# PS_control_unit_V3.net
KiCad netlist of a schematic drawn in EAGLE
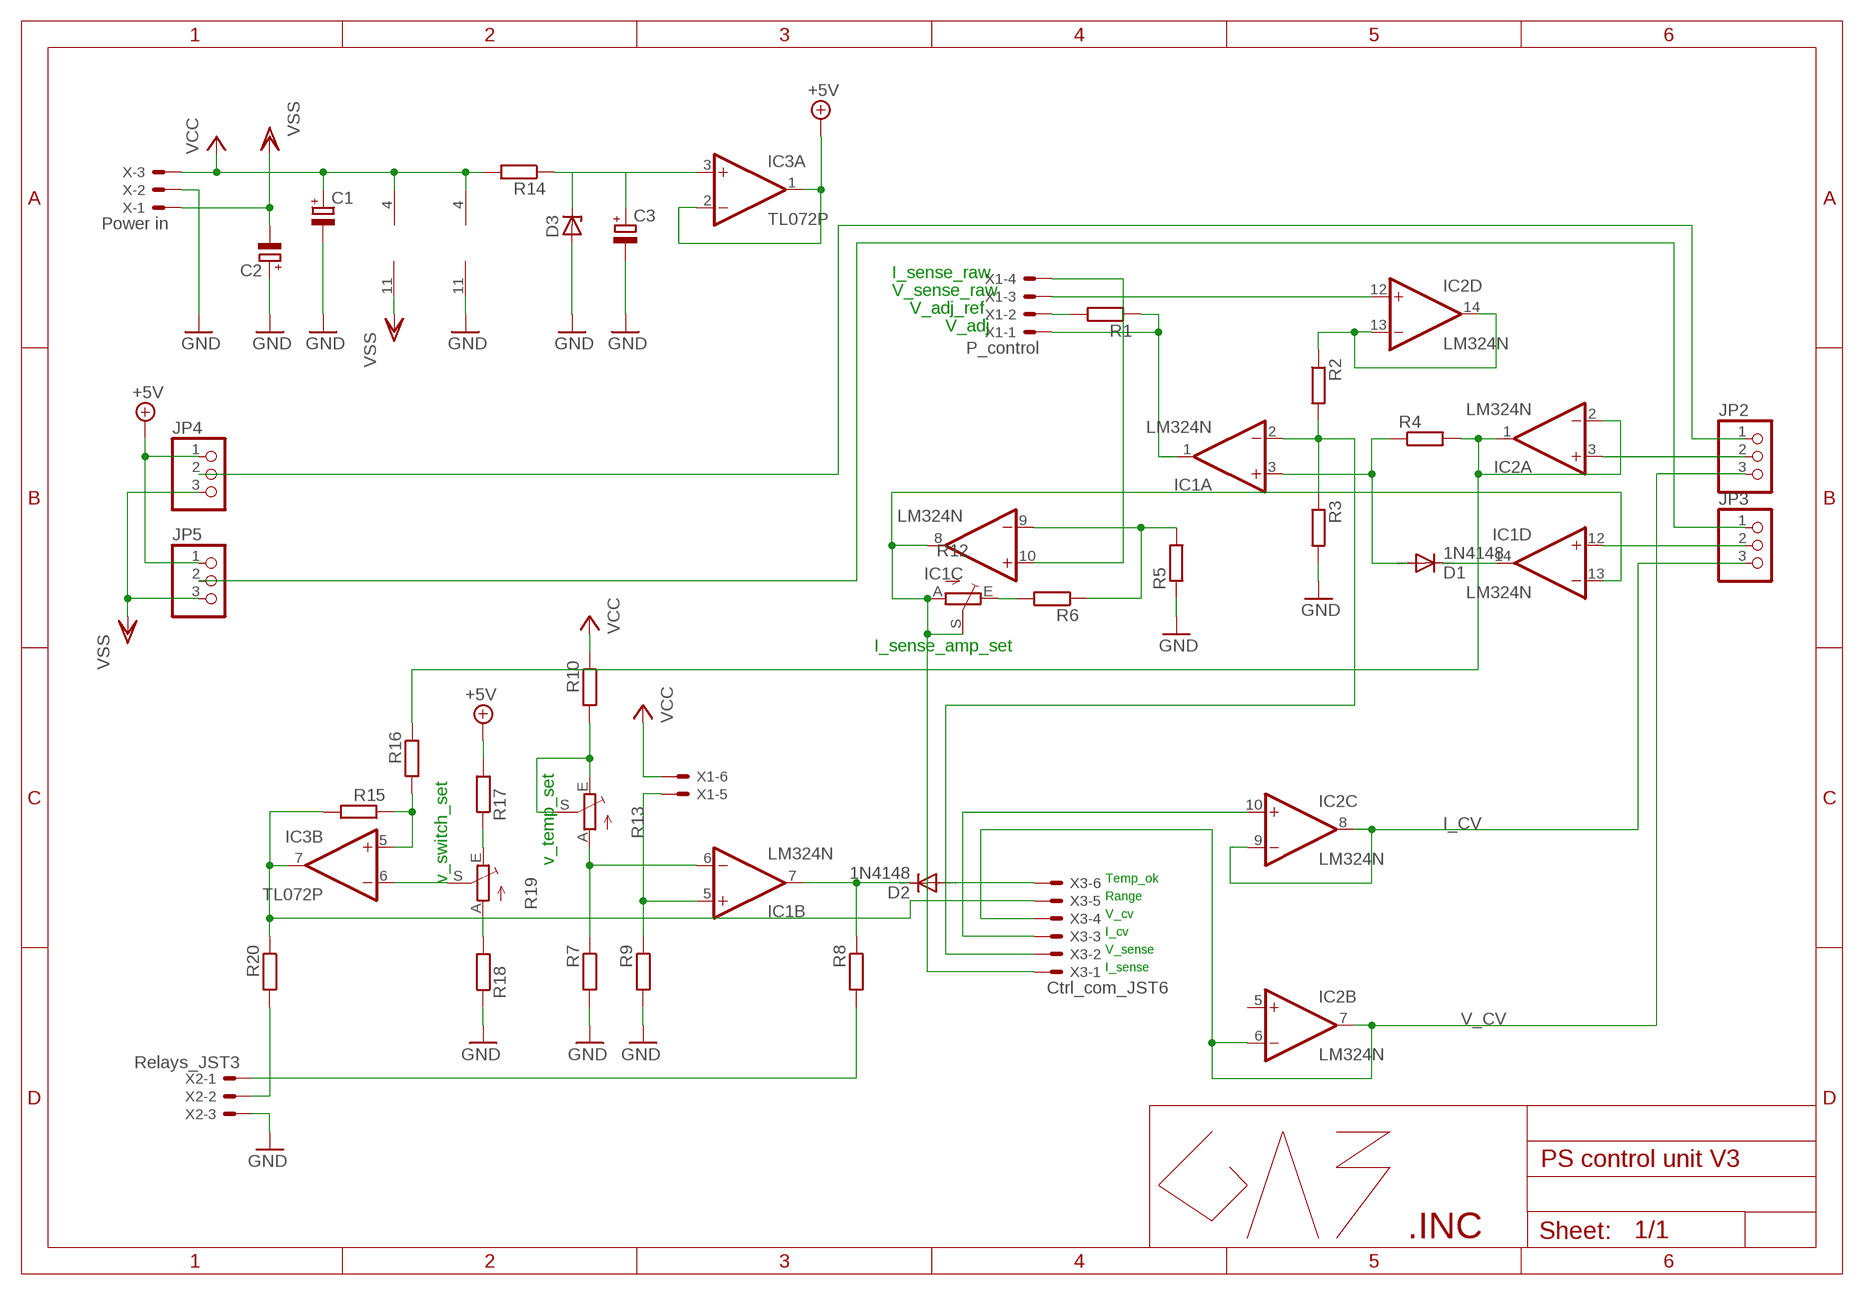
[diagram p0: schematic, sheet 1]

(export (version "E")
  (design (tool "Eeschema 10.0.6"))
  (components
    (comp (ref "C1")
      (value "CPOL-EUE2.5-7")
      (footprint "eagle-import:E2,5-7")
      (libsource (lib "eagle-import") (part "CPOL-EUE2.5-7"))
    )
    (comp (ref "C2")
      (value "CPOL-EUE2-5")
      (footprint "eagle-import:E2-5")
      (libsource (lib "eagle-import") (part "CPOL-EUE2-5"))
    )
    (comp (ref "C3")
      (value "CPOL-EUE2-5")
      (footprint "eagle-import:E2-5")
      (libsource (lib "eagle-import") (part "CPOL-EUE2-5"))
    )
    (comp (ref "D1")
      (value "1N4148")
      (footprint "eagle-import:DO35-10")
      (libsource (lib "eagle-import") (part "1N4148DO35-10"))
    )
    (comp (ref "D2")
      (value "1N4148")
      (footprint "eagle-import:DO35-10")
      (libsource (lib "eagle-import") (part "1N4148DO35-10"))
    )
    (comp (ref "D3")
      (value "ZENER-DIODEDO35Z10")
      (footprint "eagle-import:DO35Z10")
      (libsource (lib "eagle-import") (part "ZENER-DIODEDO35Z10"))
    )
    (comp (ref "IC1")
      (value "LM324N")
      (footprint "eagle-import:DIL14")
      (libsource (lib "eagle-import") (part "LM324N"))
    )
    (comp (ref "IC2")
      (value "LM324N")
      (footprint "eagle-import:DIL14")
      (libsource (lib "eagle-import") (part "LM324N"))
    )
    (comp (ref "IC3")
      (value "TL072P")
      (footprint "eagle-import:DIL08")
      (libsource (lib "eagle-import") (part "TL072P"))
    )
    (comp (ref "JP2")
      (value "PINHD-1X3")
      (footprint "eagle-import:1X03")
      (libsource (lib "eagle-import") (part "PINHD-1X3"))
    )
    (comp (ref "JP3")
      (value "PINHD-1X3")
      (footprint "eagle-import:1X03")
      (libsource (lib "eagle-import") (part "PINHD-1X3"))
    )
    (comp (ref "JP4")
      (value "PINHD-1X3")
      (footprint "eagle-import:1X03")
      (libsource (lib "eagle-import") (part "PINHD-1X3"))
    )
    (comp (ref "JP5")
      (value "PINHD-1X3")
      (footprint "eagle-import:1X03")
      (libsource (lib "eagle-import") (part "PINHD-1X3"))
    )
    (comp (ref "R1")
      (value "R-EU_0309/12")
      (footprint "eagle-import:0309_12")
      (libsource (lib "eagle-import") (part "R-EU_0309/12"))
    )
    (comp (ref "R2")
      (value "R-EU_0207/10")
      (footprint "eagle-import:0207_10")
      (libsource (lib "eagle-import") (part "R-EU_0207/10"))
    )
    (comp (ref "R3")
      (value "R-EU_0207/10")
      (footprint "eagle-import:0207_10")
      (libsource (lib "eagle-import") (part "R-EU_0207/10"))
    )
    (comp (ref "R4")
      (value "R-EU_0207/10")
      (footprint "eagle-import:0207_10")
      (libsource (lib "eagle-import") (part "R-EU_0207/10"))
    )
    (comp (ref "R5")
      (value "R-EU_0207/10")
      (footprint "eagle-import:0207_10")
      (libsource (lib "eagle-import") (part "R-EU_0207/10"))
    )
    (comp (ref "R6")
      (value "R-EU_0207/10")
      (footprint "eagle-import:0207_10")
      (libsource (lib "eagle-import") (part "R-EU_0207/10"))
    )
    (comp (ref "R7")
      (value "R-EU_0207/10")
      (footprint "eagle-import:0207_10")
      (libsource (lib "eagle-import") (part "R-EU_0207/10"))
    )
    (comp (ref "R8")
      (value "R-EU_0207/10")
      (footprint "eagle-import:0207_10")
      (libsource (lib "eagle-import") (part "R-EU_0207/10"))
    )
    (comp (ref "R9")
      (value "R-EU_0207/10")
      (footprint "eagle-import:0207_10")
      (libsource (lib "eagle-import") (part "R-EU_0207/10"))
    )
    (comp (ref "R10")
      (value "R-EU_0207/10")
      (footprint "eagle-import:0207_10")
      (libsource (lib "eagle-import") (part "R-EU_0207/10"))
    )
    (comp (ref "R12")
      (value "TRIM_EU-S64W")
      (footprint "eagle-import:S64W")
      (libsource (lib "eagle-import") (part "TRIM_EU-S64W"))
    )
    (comp (ref "R13")
      (value "TRIM_EU-S64W")
      (footprint "eagle-import:S64W")
      (libsource (lib "eagle-import") (part "TRIM_EU-S64W"))
    )
    (comp (ref "R14")
      (value "R-EU_0309/12")
      (footprint "eagle-import:0309_12")
      (libsource (lib "eagle-import") (part "R-EU_0309/12"))
    )
    (comp (ref "R15")
      (value "R-EU_0207/10")
      (footprint "eagle-import:0207_10")
      (libsource (lib "eagle-import") (part "R-EU_0207/10"))
    )
    (comp (ref "R16")
      (value "R-EU_0207/10")
      (footprint "eagle-import:0207_10")
      (libsource (lib "eagle-import") (part "R-EU_0207/10"))
    )
    (comp (ref "R17")
      (value "R-EU_0207/10")
      (footprint "eagle-import:0207_10")
      (libsource (lib "eagle-import") (part "R-EU_0207/10"))
    )
    (comp (ref "R18")
      (value "R-EU_0207/10")
      (footprint "eagle-import:0207_10")
      (libsource (lib "eagle-import") (part "R-EU_0207/10"))
    )
    (comp (ref "R19")
      (value "TRIM_EU-S64W")
      (footprint "eagle-import:S64W")
      (libsource (lib "eagle-import") (part "TRIM_EU-S64W"))
    )
    (comp (ref "R20")
      (value "R-EU_0207/10")
      (footprint "eagle-import:0207_10")
      (libsource (lib "eagle-import") (part "R-EU_0207/10"))
    )
    (comp (ref "X")
      (value "Power in")
      (footprint "eagle-import:JST-XH-03-PACKAGE-LONG-PAD")
      (libsource (lib "eagle-import") (part "JST-XH-03-PIN-LONG-PAD"))
    )
    (comp (ref "X1")
      (value "P_control")
      (footprint "eagle-import:JST-XH-06-PACKAGE-LONG-PAD")
      (libsource (lib "eagle-import") (part "JST-XH-06-PIN-LONG-PAD"))
    )
    (comp (ref "X2")
      (value "Relays_JST3")
      (footprint "eagle-import:JST-XH-03-PACKAGE-LONG-PAD")
      (libsource (lib "eagle-import") (part "JST-XH-03-PIN-LONG-PAD"))
    )
    (comp (ref "X3")
      (value "Ctrl_com_JST6")
      (footprint "eagle-import:JST-XH-06-PACKAGE-LONG-PAD")
      (libsource (lib "eagle-import") (part "JST-XH-06-PIN-LONG-PAD"))
    )
  )
  (nets
    (net (code "1") (name "+5V") (class "Default")
      (node (ref "IC3") (pin "1") (pinfunction "OUT_1") (pintype "output"))
      (node (ref "IC3") (pin "2") (pinfunction "-IN_2") (pintype "input"))
      (node (ref "JP4") (pin "1") (pinfunction "1_1") (pintype "passive"))
      (node (ref "JP5") (pin "1") (pinfunction "1_1") (pintype "passive"))
      (node (ref "R17") (pin "2") (pinfunction "2_2") (pintype "passive"))
    )
    (net (code "2") (name "/I_CV") (class "Default")
      (node (ref "IC2") (pin "8") (pinfunction "OUT_8") (pintype "output"))
      (node (ref "IC2") (pin "9") (pinfunction "-IN_9") (pintype "input"))
      (node (ref "JP3") (pin "3") (pinfunction "3_3") (pintype "passive"))
    )
    (net (code "3") (name "/V_CV") (class "Default")
      (node (ref "IC2") (pin "6") (pinfunction "-IN_6") (pintype "input"))
      (node (ref "IC2") (pin "7") (pinfunction "OUT_7") (pintype "output"))
      (node (ref "JP2") (pin "3") (pinfunction "3_3") (pintype "passive"))
      (node (ref "X3") (pin "4") (pinfunction "S_4") (pintype "passive"))
    )
    (net (code "4") (name "GND") (class "Default")
      (node (ref "C1") (pin "-") (pinfunction "-_-") (pintype "passive"))
      (node (ref "C2") (pin "+") (pinfunction "+_+") (pintype "passive"))
      (node (ref "C3") (pin "-") (pinfunction "-_-") (pintype "passive"))
      (node (ref "D3") (pin "A") (pinfunction "A_A") (pintype "passive"))
      (node (ref "IC2") (pin "11") (pinfunction "V-_11") (pintype "power_in"))
      (node (ref "R18") (pin "1") (pinfunction "1_1") (pintype "passive"))
      (node (ref "R3") (pin "2") (pinfunction "2_2") (pintype "passive"))
      (node (ref "R5") (pin "1") (pinfunction "1_1") (pintype "passive"))
      (node (ref "R7") (pin "2") (pinfunction "2_2") (pintype "passive"))
      (node (ref "R9") (pin "2") (pinfunction "2_2") (pintype "passive"))
      (node (ref "X") (pin "2") (pinfunction "S_2") (pintype "passive"))
      (node (ref "X2") (pin "3") (pinfunction "S_3") (pintype "passive"))
    )
    (net (code "5") (name "Net-(IC1A-+IN)") (class "Default")
      (node (ref "D1") (pin "A") (pinfunction "A_A") (pintype "passive"))
      (node (ref "IC1") (pin "3") (pinfunction "+IN_3") (pintype "input"))
      (node (ref "R4") (pin "1") (pinfunction "1_1") (pintype "passive"))
    )
    (net (code "6") (name "Net-(IC1A--IN)") (class "Default")
      (node (ref "IC1") (pin "2") (pinfunction "-IN_2") (pintype "input"))
      (node (ref "R2") (pin "2") (pinfunction "2_2") (pintype "passive"))
      (node (ref "R3") (pin "1") (pinfunction "1_1") (pintype "passive"))
      (node (ref "X3") (pin "2") (pinfunction "S_2") (pintype "passive"))
    )
    (net (code "7") (name "Net-(IC1A-OUT)") (class "Default")
      (node (ref "IC1") (pin "1") (pinfunction "OUT_1") (pintype "output"))
      (node (ref "R1") (pin "1") (pinfunction "1_1") (pintype "passive"))
      (node (ref "X1") (pin "1") (pinfunction "S_1") (pintype "passive"))
    )
    (net (code "8") (name "Net-(IC1B-+IN)") (class "Default")
      (node (ref "IC1") (pin "5") (pinfunction "+IN_5") (pintype "input"))
      (node (ref "R9") (pin "1") (pinfunction "1_1") (pintype "passive"))
      (node (ref "X1") (pin "5") (pinfunction "S_5") (pintype "passive"))
    )
    (net (code "9") (name "Net-(IC1B--IN)") (class "Default")
      (node (ref "IC1") (pin "6") (pinfunction "-IN_6") (pintype "input"))
      (node (ref "R13") (pin "A") (pinfunction "A_A") (pintype "passive"))
      (node (ref "R7") (pin "1") (pinfunction "1_1") (pintype "passive"))
    )
    (net (code "10") (name "Net-(IC1B-OUT)") (class "Default")
      (node (ref "D2") (pin "C") (pinfunction "C_C") (pintype "passive"))
      (node (ref "IC1") (pin "7") (pinfunction "OUT_7") (pintype "output"))
      (node (ref "R8") (pin "1") (pinfunction "1_1") (pintype "passive"))
    )
    (net (code "11") (name "Net-(IC1C-+IN)") (class "Default")
      (node (ref "IC1") (pin "10") (pinfunction "+IN_10") (pintype "input"))
      (node (ref "X1") (pin "4") (pinfunction "S_4") (pintype "passive"))
    )
    (net (code "12") (name "Net-(IC1C--IN)") (class "Default")
      (node (ref "IC1") (pin "9") (pinfunction "-IN_9") (pintype "input"))
      (node (ref "R5") (pin "2") (pinfunction "2_2") (pintype "passive"))
      (node (ref "R6") (pin "1") (pinfunction "1_1") (pintype "passive"))
    )
    (net (code "13") (name "Net-(IC1C-OUT)") (class "Default")
      (node (ref "IC1") (pin "13") (pinfunction "-IN_13") (pintype "input"))
      (node (ref "IC1") (pin "8") (pinfunction "OUT_8") (pintype "output"))
      (node (ref "R12") (pin "A") (pinfunction "A_A") (pintype "passive"))
      (node (ref "R12") (pin "S") (pinfunction "S_S") (pintype "passive"))
      (node (ref "X3") (pin "1") (pinfunction "S_1") (pintype "passive"))
    )
    (net (code "14") (name "Net-(IC1D-+IN)") (class "Default")
      (node (ref "IC1") (pin "12") (pinfunction "+IN_12") (pintype "input"))
      (node (ref "JP3") (pin "2") (pinfunction "2_2") (pintype "passive"))
    )
    (net (code "15") (name "Net-(IC1D-OUT)") (class "Default")
      (node (ref "D1") (pin "C") (pinfunction "C_C") (pintype "passive"))
      (node (ref "IC1") (pin "14") (pinfunction "OUT_14") (pintype "output"))
    )
    (net (code "16") (name "Net-(IC2A-+IN)") (class "Default")
      (node (ref "IC2") (pin "3") (pinfunction "+IN_3") (pintype "input"))
      (node (ref "JP2") (pin "2") (pinfunction "2_2") (pintype "passive"))
    )
    (net (code "17") (name "Net-(IC2A--IN)") (class "Default")
      (node (ref "IC2") (pin "1") (pinfunction "OUT_1") (pintype "output"))
      (node (ref "IC2") (pin "2") (pinfunction "-IN_2") (pintype "input"))
      (node (ref "R16") (pin "1") (pinfunction "1_1") (pintype "passive"))
      (node (ref "R4") (pin "2") (pinfunction "2_2") (pintype "passive"))
    )
    (net (code "18") (name "Net-(IC2C-+IN)") (class "Default")
      (node (ref "IC2") (pin "10") (pinfunction "+IN_10") (pintype "input"))
      (node (ref "X3") (pin "3") (pinfunction "S_3") (pintype "passive"))
    )
    (net (code "19") (name "Net-(IC2D-+IN)") (class "Default")
      (node (ref "IC2") (pin "12") (pinfunction "+IN_12") (pintype "input"))
      (node (ref "X1") (pin "3") (pinfunction "S_3") (pintype "passive"))
    )
    (net (code "20") (name "Net-(IC2D--IN)") (class "Default")
      (node (ref "IC2") (pin "13") (pinfunction "-IN_13") (pintype "input"))
      (node (ref "IC2") (pin "14") (pinfunction "OUT_14") (pintype "output"))
      (node (ref "R2") (pin "1") (pinfunction "1_1") (pintype "passive"))
    )
    (net (code "21") (name "Net-(IC3A-+IN)") (class "Default")
      (node (ref "C3") (pin "+") (pinfunction "+_+") (pintype "passive"))
      (node (ref "D3") (pin "C") (pinfunction "C_C") (pintype "passive"))
      (node (ref "IC3") (pin "3") (pinfunction "+IN_3") (pintype "input"))
      (node (ref "R14") (pin "1") (pinfunction "1_1") (pintype "passive"))
    )
    (net (code "22") (name "Net-(IC3B-+IN)") (class "Default")
      (node (ref "IC3") (pin "5") (pinfunction "+IN_5") (pintype "input"))
      (node (ref "R15") (pin "1") (pinfunction "1_1") (pintype "passive"))
      (node (ref "R16") (pin "2") (pinfunction "2_2") (pintype "passive"))
    )
    (net (code "23") (name "Net-(IC3B--IN)") (class "Default")
      (node (ref "IC3") (pin "6") (pinfunction "-IN_6") (pintype "input"))
      (node (ref "R19") (pin "S") (pinfunction "S_S") (pintype "passive"))
    )
    (net (code "24") (name "Net-(IC3B-OUT)") (class "Default")
      (node (ref "IC3") (pin "7") (pinfunction "OUT_7") (pintype "output"))
      (node (ref "R15") (pin "2") (pinfunction "2_2") (pintype "passive"))
      (node (ref "R20") (pin "1") (pinfunction "1_1") (pintype "passive"))
      (node (ref "X3") (pin "5") (pinfunction "S_5") (pintype "passive"))
    )
    (net (code "25") (name "Net-(JP2-Pad1)") (class "Default")
      (node (ref "JP2") (pin "1") (pinfunction "1_1") (pintype "passive"))
      (node (ref "JP4") (pin "2") (pinfunction "2_2") (pintype "passive"))
    )
    (net (code "26") (name "Net-(JP3-Pad1)") (class "Default")
      (node (ref "JP3") (pin "1") (pinfunction "1_1") (pintype "passive"))
      (node (ref "JP5") (pin "2") (pinfunction "2_2") (pintype "passive"))
    )
    (net (code "27") (name "Net-(R10-Pad2)") (class "Default")
      (node (ref "R10") (pin "2") (pinfunction "2_2") (pintype "passive"))
      (node (ref "R13") (pin "E") (pinfunction "E_E") (pintype "passive"))
      (node (ref "R13") (pin "S") (pinfunction "S_S") (pintype "passive"))
    )
    (net (code "28") (name "Net-(R12-PadE)") (class "Default")
      (node (ref "R12") (pin "E") (pinfunction "E_E") (pintype "passive"))
      (node (ref "R6") (pin "2") (pinfunction "2_2") (pintype "passive"))
    )
    (net (code "29") (name "Net-(R17-Pad1)") (class "Default")
      (node (ref "R17") (pin "1") (pinfunction "1_1") (pintype "passive"))
      (node (ref "R19") (pin "E") (pinfunction "E_E") (pintype "passive"))
    )
    (net (code "30") (name "Net-(R18-Pad2)") (class "Default")
      (node (ref "R18") (pin "2") (pinfunction "2_2") (pintype "passive"))
      (node (ref "R19") (pin "A") (pinfunction "A_A") (pintype "passive"))
    )
    (net (code "31") (name "Net-(X1B-S)") (class "Default")
      (node (ref "R1") (pin "2") (pinfunction "2_2") (pintype "passive"))
      (node (ref "X1") (pin "2") (pinfunction "S_2") (pintype "passive"))
    )
    (net (code "32") (name "Net-(X2A-S)") (class "Default")
      (node (ref "R8") (pin "2") (pinfunction "2_2") (pintype "passive"))
      (node (ref "X2") (pin "1") (pinfunction "S_1") (pintype "passive"))
    )
    (net (code "33") (name "Net-(X2B-S)") (class "Default")
      (node (ref "R20") (pin "2") (pinfunction "2_2") (pintype "passive"))
      (node (ref "X2") (pin "2") (pinfunction "S_2") (pintype "passive"))
    )
    (net (code "34") (name "Net-(X3F-S)") (class "Default")
      (node (ref "D2") (pin "A") (pinfunction "A_A") (pintype "passive"))
      (node (ref "X3") (pin "6") (pinfunction "S_6") (pintype "passive"))
    )
    (net (code "35") (name "VCC") (class "Default")
      (node (ref "C1") (pin "+") (pinfunction "+_+") (pintype "passive"))
      (node (ref "IC1") (pin "4") (pinfunction "V+_4") (pintype "power_in"))
      (node (ref "IC2") (pin "4") (pinfunction "V+_4") (pintype "power_in"))
      (node (ref "R10") (pin "1") (pinfunction "1_1") (pintype "passive"))
      (node (ref "R14") (pin "2") (pinfunction "2_2") (pintype "passive"))
      (node (ref "X") (pin "3") (pinfunction "S_3") (pintype "passive"))
      (node (ref "X1") (pin "6") (pinfunction "S_6") (pintype "passive"))
    )
    (net (code "36") (name "VSS") (class "Default")
      (node (ref "C2") (pin "-") (pinfunction "-_-") (pintype "passive"))
      (node (ref "IC1") (pin "11") (pinfunction "V-_11") (pintype "power_in"))
      (node (ref "JP4") (pin "3") (pinfunction "3_3") (pintype "passive"))
      (node (ref "JP5") (pin "3") (pinfunction "3_3") (pintype "passive"))
      (node (ref "X") (pin "1") (pinfunction "S_1") (pintype "passive"))
    )
    (net (code "37") (name "unconnected-(IC2B-+IN-Pad5)") (class "Default")
      (node (ref "IC2") (pin "5") (pinfunction "+IN_5") (pintype "input"))
    )
  )
)
